# attiny84.net
KiCad netlist of a schematic drawn in EAGLE
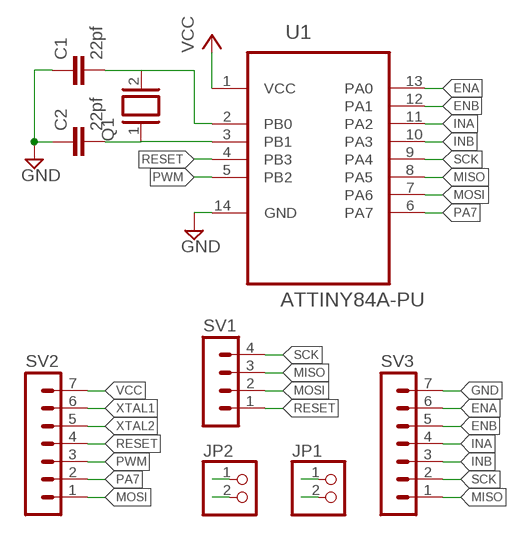
[diagram p0: schematic, sheet 1]

(export (version "E")
  (design (tool "Eeschema 10.0.6"))
  (components
    (comp (ref "C1")
      (value "22pf")
      (footprint "eagle-import:C2.5-2")
      (libsource (lib "eagle-import") (part "C2.5/2"))
    )
    (comp (ref "C2")
      (value "22pf")
      (footprint "eagle-import:C2.5-2")
      (libsource (lib "eagle-import") (part "C2.5/2"))
    )
    (comp (ref "JP1")
      (value "PINHD-1X2")
      (footprint "eagle-import:1X02")
      (libsource (lib "eagle-import") (part "PINHD-1X2"))
    )
    (comp (ref "JP2")
      (value "PINHD-1X2")
      (footprint "eagle-import:1X02")
      (libsource (lib "eagle-import") (part "PINHD-1X2"))
    )
    (comp (ref "Q1")
      (value "XTAL/S")
      (footprint "eagle-import:QS")
      (libsource (lib "eagle-import") (part "XTAL/S"))
    )
    (comp (ref "SV1")
      (value "MA04-1")
      (footprint "eagle-import:MA04-1")
      (libsource (lib "eagle-import") (part "MA04-1"))
    )
    (comp (ref "SV2")
      (value "MA07-1")
      (footprint "eagle-import:MA07-1")
      (libsource (lib "eagle-import") (part "MA07-1"))
    )
    (comp (ref "SV3")
      (value "MA07-1")
      (footprint "eagle-import:MA07-1")
      (libsource (lib "eagle-import") (part "MA07-1"))
    )
    (comp (ref "U1")
      (value "ATTINY84A-PU")
      (footprint "eagle-import:DIP254P762X533-14")
      (libsource (lib "eagle-import") (part "ATTINY84A-PU"))
    )
  )
  (nets
    (net (code "1") (name "ENA") (class "Default")
      (node (ref "SV3") (pin "6") (pinfunction "6_6") (pintype "passive"))
      (node (ref "U1") (pin "13") (pinfunction "PA0_13") (pintype "bidirectional"))
    )
    (net (code "2") (name "ENB") (class "Default")
      (node (ref "SV3") (pin "5") (pinfunction "5_5") (pintype "passive"))
      (node (ref "U1") (pin "12") (pinfunction "PA1_12") (pintype "bidirectional"))
    )
    (net (code "3") (name "GND") (class "Default")
      (node (ref "C1") (pin "1") (pinfunction "1_1") (pintype "passive"))
      (node (ref "C2") (pin "1") (pinfunction "1_1") (pintype "passive"))
      (node (ref "JP1") (pin "1") (pinfunction "1_1") (pintype "passive"))
      (node (ref "JP1") (pin "2") (pinfunction "2_2") (pintype "passive"))
      (node (ref "SV3") (pin "7") (pinfunction "7_7") (pintype "passive"))
      (node (ref "U1") (pin "14") (pinfunction "GND_14") (pintype "passive"))
    )
    (net (code "4") (name "INA") (class "Default")
      (node (ref "SV3") (pin "4") (pinfunction "4_4") (pintype "passive"))
      (node (ref "U1") (pin "11") (pinfunction "PA2_11") (pintype "bidirectional"))
    )
    (net (code "5") (name "INB") (class "Default")
      (node (ref "SV3") (pin "3") (pinfunction "3_3") (pintype "passive"))
      (node (ref "U1") (pin "10") (pinfunction "PA3_10") (pintype "bidirectional"))
    )
    (net (code "6") (name "MISO") (class "Default")
      (node (ref "SV1") (pin "3") (pinfunction "3_3") (pintype "passive"))
      (node (ref "SV3") (pin "1") (pinfunction "1_1") (pintype "passive"))
      (node (ref "U1") (pin "8") (pinfunction "PA5_8") (pintype "bidirectional"))
    )
    (net (code "7") (name "MOSI") (class "Default")
      (node (ref "SV1") (pin "2") (pinfunction "2_2") (pintype "passive"))
      (node (ref "SV2") (pin "1") (pinfunction "1_1") (pintype "passive"))
      (node (ref "U1") (pin "7") (pinfunction "PA6_7") (pintype "bidirectional"))
    )
    (net (code "8") (name "PA7") (class "Default")
      (node (ref "SV2") (pin "2") (pinfunction "2_2") (pintype "passive"))
      (node (ref "U1") (pin "6") (pinfunction "PA7_6") (pintype "bidirectional"))
    )
    (net (code "9") (name "PWM") (class "Default")
      (node (ref "SV2") (pin "3") (pinfunction "3_3") (pintype "passive"))
      (node (ref "U1") (pin "5") (pinfunction "PB2_5") (pintype "bidirectional"))
    )
    (net (code "10") (name "RESET") (class "Default")
      (node (ref "SV1") (pin "1") (pinfunction "1_1") (pintype "passive"))
      (node (ref "SV2") (pin "4") (pinfunction "4_4") (pintype "passive"))
      (node (ref "U1") (pin "4") (pinfunction "PB3_4") (pintype "bidirectional"))
    )
    (net (code "11") (name "SCK") (class "Default")
      (node (ref "SV1") (pin "4") (pinfunction "4_4") (pintype "passive"))
      (node (ref "SV3") (pin "2") (pinfunction "2_2") (pintype "passive"))
      (node (ref "U1") (pin "9") (pinfunction "PA4_9") (pintype "bidirectional"))
    )
    (net (code "12") (name "VCC") (class "Default")
      (node (ref "JP2") (pin "1") (pinfunction "1_1") (pintype "passive"))
      (node (ref "JP2") (pin "2") (pinfunction "2_2") (pintype "passive"))
      (node (ref "SV2") (pin "7") (pinfunction "7_7") (pintype "passive"))
      (node (ref "U1") (pin "1") (pinfunction "VCC_1") (pintype "power_in"))
    )
    (net (code "13") (name "XTAL1") (class "Default")
      (node (ref "C1") (pin "2") (pinfunction "2_2") (pintype "passive"))
      (node (ref "Q1") (pin "2") (pinfunction "2_2") (pintype "passive"))
      (node (ref "SV2") (pin "6") (pinfunction "6_6") (pintype "passive"))
      (node (ref "U1") (pin "2") (pinfunction "PB0_2") (pintype "bidirectional"))
    )
    (net (code "14") (name "XTAL2") (class "Default")
      (node (ref "C2") (pin "2") (pinfunction "2_2") (pintype "passive"))
      (node (ref "Q1") (pin "1") (pinfunction "1_1") (pintype "passive"))
      (node (ref "SV2") (pin "5") (pinfunction "5_5") (pintype "passive"))
      (node (ref "U1") (pin "3") (pinfunction "PB1_3") (pintype "bidirectional"))
    )
  )
)
